# Schematic.net
KiCad netlist of a schematic drawn in EAGLE
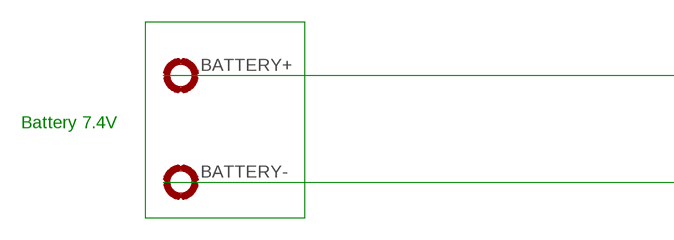
[diagram p0: schematic, sheet 1, part 1 of 2]
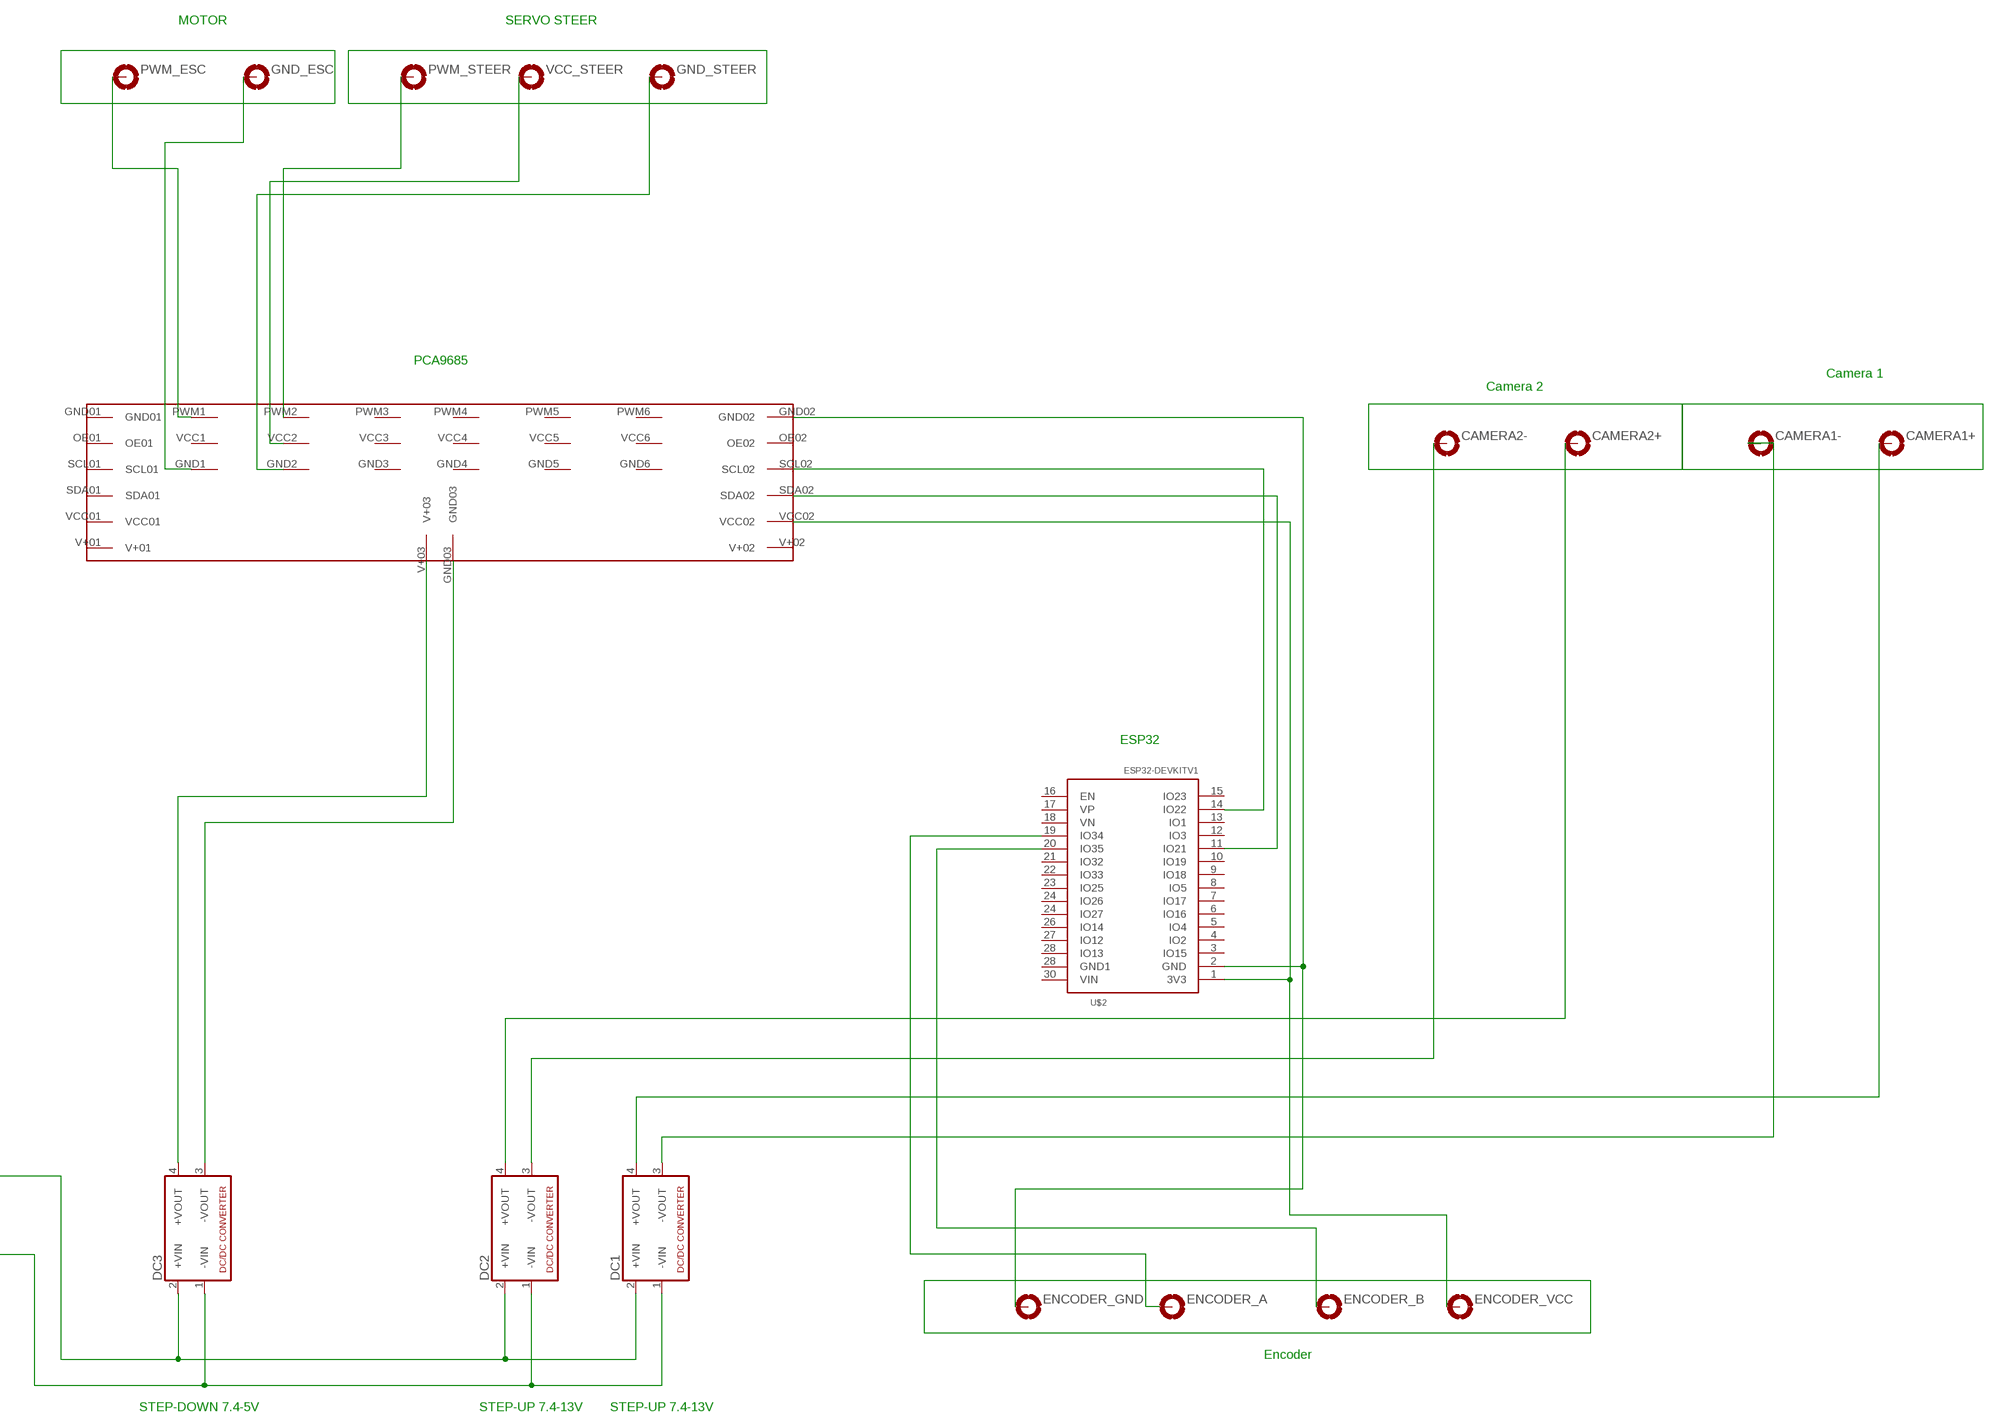
[diagram p1: schematic, sheet 1, part 2 of 2]

(export (version "E")
  (design (tool "Eeschema 10.0.6"))
  (components
    (comp (ref "BATTERY+")
      (value "MOUNT-PAD-ROUND2.8")
      (footprint "eagle-import:2,8-PAD")
      (libsource (lib "eagle-import") (part "MOUNT-PAD-ROUND2.8"))
    )
    (comp (ref "BATTERY-")
      (value "MOUNT-PAD-ROUND2.8")
      (footprint "eagle-import:2,8-PAD")
      (libsource (lib "eagle-import") (part "MOUNT-PAD-ROUND2.8"))
    )
    (comp (ref "CAMERA1+")
      (value "MOUNT-PAD-ROUND2.8")
      (footprint "eagle-import:2,8-PAD")
      (libsource (lib "eagle-import") (part "MOUNT-PAD-ROUND2.8"))
    )
    (comp (ref "CAMERA1-")
      (value "MOUNT-PAD-ROUND2.8")
      (footprint "eagle-import:2,8-PAD")
      (libsource (lib "eagle-import") (part "MOUNT-PAD-ROUND2.8"))
    )
    (comp (ref "CAMERA2+")
      (value "MOUNT-PAD-ROUND2.8")
      (footprint "eagle-import:2,8-PAD")
      (libsource (lib "eagle-import") (part "MOUNT-PAD-ROUND2.8"))
    )
    (comp (ref "CAMERA2-")
      (value "MOUNT-PAD-ROUND2.8")
      (footprint "eagle-import:2,8-PAD")
      (libsource (lib "eagle-import") (part "MOUNT-PAD-ROUND2.8"))
    )
    (comp (ref "DC1")
      (value "NME")
      (footprint "eagle-import:NME")
      (fields (field (name "MF") "C & D TECHNOLOGIES, INC") (field (name "MPN") "NME1205D"))
      (libsource (lib "eagle-import") (part "NME"))
    )
    (comp (ref "DC2")
      (value "NME")
      (footprint "eagle-import:NME")
      (fields (field (name "MF") "C & D TECHNOLOGIES, INC") (field (name "MPN") "NME1205D"))
      (libsource (lib "eagle-import") (part "NME"))
    )
    (comp (ref "DC3")
      (value "NME")
      (footprint "eagle-import:NME")
      (fields (field (name "MF") "C & D TECHNOLOGIES, INC") (field (name "MPN") "NME1205D"))
      (libsource (lib "eagle-import") (part "NME"))
    )
    (comp (ref "ENCODER_A")
      (value "MOUNT-PAD-ROUND2.8")
      (footprint "eagle-import:2,8-PAD")
      (libsource (lib "eagle-import") (part "MOUNT-PAD-ROUND2.8"))
    )
    (comp (ref "ENCODER_B")
      (value "MOUNT-PAD-ROUND2.8")
      (footprint "eagle-import:2,8-PAD")
      (libsource (lib "eagle-import") (part "MOUNT-PAD-ROUND2.8"))
    )
    (comp (ref "ENCODER_GND")
      (value "MOUNT-PAD-ROUND2.8")
      (footprint "eagle-import:2,8-PAD")
      (libsource (lib "eagle-import") (part "MOUNT-PAD-ROUND2.8"))
    )
    (comp (ref "ENCODER_VCC")
      (value "MOUNT-PAD-ROUND2.8")
      (footprint "eagle-import:2,8-PAD")
      (libsource (lib "eagle-import") (part "MOUNT-PAD-ROUND2.8"))
    )
    (comp (ref "GND_ESC")
      (value "MOUNT-PAD-ROUND2.8")
      (footprint "eagle-import:2,8-PAD")
      (libsource (lib "eagle-import") (part "MOUNT-PAD-ROUND2.8"))
    )
    (comp (ref "GND_STEER")
      (value "MOUNT-PAD-ROUND2.8")
      (footprint "eagle-import:2,8-PAD")
      (libsource (lib "eagle-import") (part "MOUNT-PAD-ROUND2.8"))
    )
    (comp (ref "PWM_ESC")
      (value "MOUNT-PAD-ROUND2.8")
      (footprint "eagle-import:2,8-PAD")
      (libsource (lib "eagle-import") (part "MOUNT-PAD-ROUND2.8"))
    )
    (comp (ref "PWM_STEER")
      (value "MOUNT-PAD-ROUND2.8")
      (footprint "eagle-import:2,8-PAD")
      (libsource (lib "eagle-import") (part "MOUNT-PAD-ROUND2.8"))
    )
    (comp (ref "U$1")
      (value "PCA9685PCA9685")
      (footprint "eagle-import:DIP5918W53P254L2279H300Q12B")
      (libsource (lib "eagle-import") (part "PCA9685PCA9685"))
    )
    (comp (ref "U$2")
      (value "ESP32DEVKITV1")
      (footprint "eagle-import:ESP32-DEVKITV1")
      (libsource (lib "eagle-import") (part "ESP32DEVKITV1"))
    )
    (comp (ref "VCC_STEER")
      (value "MOUNT-PAD-ROUND2.8")
      (footprint "eagle-import:2,8-PAD")
      (libsource (lib "eagle-import") (part "MOUNT-PAD-ROUND2.8"))
    )
  )
  (nets
    (net (code "1") (name "Net-(BATTERY+-MOUNT)") (class "Default")
      (node (ref "BATTERY+") (pin "B2,8") (pinfunction "MOUNT_B2,8") (pintype "passive"))
      (node (ref "DC1") (pin "2") (pinfunction "+VIN_2") (pintype "passive"))
      (node (ref "DC2") (pin "2") (pinfunction "+VIN_2") (pintype "passive"))
      (node (ref "DC3") (pin "2") (pinfunction "+VIN_2") (pintype "passive"))
    )
    (net (code "2") (name "Net-(BATTERY--MOUNT)") (class "Default")
      (node (ref "BATTERY-") (pin "B2,8") (pinfunction "MOUNT_B2,8") (pintype "passive"))
      (node (ref "DC1") (pin "1") (pinfunction "-VIN_1") (pintype "passive"))
      (node (ref "DC2") (pin "1") (pinfunction "-VIN_1") (pintype "passive"))
      (node (ref "DC3") (pin "1") (pinfunction "-VIN_1") (pintype "passive"))
    )
    (net (code "3") (name "Net-(CAMERA1+-MOUNT)") (class "Default")
      (node (ref "CAMERA1+") (pin "B2,8") (pinfunction "MOUNT_B2,8") (pintype "passive"))
      (node (ref "DC1") (pin "4") (pinfunction "+VOUT_4") (pintype "passive"))
    )
    (net (code "4") (name "Net-(CAMERA1--MOUNT)") (class "Default")
      (node (ref "CAMERA1-") (pin "B2,8") (pinfunction "MOUNT_B2,8") (pintype "passive"))
      (node (ref "DC1") (pin "3") (pinfunction "-VOUT_3") (pintype "passive"))
    )
    (net (code "5") (name "Net-(CAMERA2+-MOUNT)") (class "Default")
      (node (ref "CAMERA2+") (pin "B2,8") (pinfunction "MOUNT_B2,8") (pintype "passive"))
      (node (ref "DC2") (pin "4") (pinfunction "+VOUT_4") (pintype "passive"))
    )
    (net (code "6") (name "Net-(CAMERA2--MOUNT)") (class "Default")
      (node (ref "CAMERA2-") (pin "B2,8") (pinfunction "MOUNT_B2,8") (pintype "passive"))
      (node (ref "DC2") (pin "3") (pinfunction "-VOUT_3") (pintype "passive"))
    )
    (net (code "7") (name "Net-(DC3-+VOUT)") (class "Default")
      (node (ref "DC3") (pin "4") (pinfunction "+VOUT_4") (pintype "passive"))
      (node (ref "U$1") (pin "V+03") (pinfunction "V+03_V+03") (pintype "bidirectional"))
    )
    (net (code "8") (name "Net-(DC3--VOUT)") (class "Default")
      (node (ref "DC3") (pin "3") (pinfunction "-VOUT_3") (pintype "passive"))
      (node (ref "U$1") (pin "GND03") (pinfunction "GND03_GND03") (pintype "bidirectional"))
    )
    (net (code "9") (name "Net-(ENCODER_A-MOUNT)") (class "Default")
      (node (ref "ENCODER_A") (pin "B2,8") (pinfunction "MOUNT_B2,8") (pintype "passive"))
      (node (ref "U$2") (pin "19") (pinfunction "IO34_19") (pintype "bidirectional"))
    )
    (net (code "10") (name "Net-(ENCODER_B-MOUNT)") (class "Default")
      (node (ref "ENCODER_B") (pin "B2,8") (pinfunction "MOUNT_B2,8") (pintype "passive"))
      (node (ref "U$2") (pin "20") (pinfunction "IO35_20") (pintype "bidirectional"))
    )
    (net (code "11") (name "Net-(ENCODER_GND-MOUNT)") (class "Default")
      (node (ref "ENCODER_GND") (pin "B2,8") (pinfunction "MOUNT_B2,8") (pintype "passive"))
      (node (ref "U$1") (pin "GND02") (pinfunction "GND02_GND02") (pintype "bidirectional"))
      (node (ref "U$2") (pin "2") (pinfunction "GND_2") (pintype "bidirectional"))
    )
    (net (code "12") (name "Net-(ENCODER_VCC-MOUNT)") (class "Default")
      (node (ref "ENCODER_VCC") (pin "B2,8") (pinfunction "MOUNT_B2,8") (pintype "passive"))
      (node (ref "U$1") (pin "VCC02") (pinfunction "VCC02_VCC02") (pintype "bidirectional"))
      (node (ref "U$2") (pin "1") (pinfunction "3V3_1") (pintype "bidirectional"))
    )
    (net (code "13") (name "Net-(GND_ESC-MOUNT)") (class "Default")
      (node (ref "GND_ESC") (pin "B2,8") (pinfunction "MOUNT_B2,8") (pintype "passive"))
      (node (ref "U$1") (pin "GND1") (pinfunction "GND$1_GND1") (pintype "bidirectional"))
    )
    (net (code "14") (name "Net-(GND_STEER-MOUNT)") (class "Default")
      (node (ref "GND_STEER") (pin "B2,8") (pinfunction "MOUNT_B2,8") (pintype "passive"))
      (node (ref "U$1") (pin "GND2") (pinfunction "GND$2_GND2") (pintype "bidirectional"))
    )
    (net (code "15") (name "Net-(PWM_ESC-MOUNT)") (class "Default")
      (node (ref "PWM_ESC") (pin "B2,8") (pinfunction "MOUNT_B2,8") (pintype "passive"))
      (node (ref "U$1") (pin "PWM1") (pinfunction "PWM$1_PWM1") (pintype "bidirectional"))
    )
    (net (code "16") (name "Net-(PWM_STEER-MOUNT)") (class "Default")
      (node (ref "PWM_STEER") (pin "B2,8") (pinfunction "MOUNT_B2,8") (pintype "passive"))
      (node (ref "U$1") (pin "PWM2") (pinfunction "PWM$2_PWM2") (pintype "bidirectional"))
    )
    (net (code "17") (name "Net-(U$1-VCC$2)") (class "Default")
      (node (ref "U$1") (pin "VCC2") (pinfunction "VCC$2_VCC2") (pintype "bidirectional"))
      (node (ref "VCC_STEER") (pin "B2,8") (pinfunction "MOUNT_B2,8") (pintype "passive"))
    )
    (net (code "18") (name "Net-(U$2-IO21)") (class "Default")
      (node (ref "U$1") (pin "SDA02") (pinfunction "SDA02_SDA02") (pintype "bidirectional"))
      (node (ref "U$2") (pin "11") (pinfunction "IO21_11") (pintype "bidirectional"))
    )
    (net (code "19") (name "Net-(U$2-IO22)") (class "Default")
      (node (ref "U$1") (pin "SCL02") (pinfunction "SCL02_SCL02") (pintype "bidirectional"))
      (node (ref "U$2") (pin "14") (pinfunction "IO22_14") (pintype "bidirectional"))
    )
    (net (code "20") (name "unconnected-(U$1-GND$3-PadGND3)") (class "Default")
      (node (ref "U$1") (pin "GND3") (pinfunction "GND$3_GND3") (pintype "bidirectional"))
    )
    (net (code "21") (name "unconnected-(U$1-GND$4-PadGND4)") (class "Default")
      (node (ref "U$1") (pin "GND4") (pinfunction "GND$4_GND4") (pintype "bidirectional"))
    )
    (net (code "22") (name "unconnected-(U$1-GND$5-PadGND5)") (class "Default")
      (node (ref "U$1") (pin "GND5") (pinfunction "GND$5_GND5") (pintype "bidirectional"))
    )
    (net (code "23") (name "unconnected-(U$1-GND$6-PadGND6)") (class "Default")
      (node (ref "U$1") (pin "GND6") (pinfunction "GND$6_GND6") (pintype "bidirectional"))
    )
    (net (code "24") (name "unconnected-(U$1-PWM$3-PadPWM3)") (class "Default")
      (node (ref "U$1") (pin "PWM3") (pinfunction "PWM$3_PWM3") (pintype "bidirectional"))
    )
    (net (code "25") (name "unconnected-(U$1-PWM$4-PadPWM4)") (class "Default")
      (node (ref "U$1") (pin "PWM4") (pinfunction "PWM$4_PWM4") (pintype "bidirectional"))
    )
    (net (code "26") (name "unconnected-(U$1-PWM$5-PadPWM5)") (class "Default")
      (node (ref "U$1") (pin "PWM5") (pinfunction "PWM$5_PWM5") (pintype "bidirectional"))
    )
    (net (code "27") (name "unconnected-(U$1-PWM$6-PadPWM6)") (class "Default")
      (node (ref "U$1") (pin "PWM6") (pinfunction "PWM$6_PWM6") (pintype "bidirectional"))
    )
    (net (code "28") (name "unconnected-(U$1-PadGND01)") (class "Default")
      (node (ref "U$1") (pin "GND01") (pinfunction "GND01_GND01") (pintype "bidirectional"))
    )
    (net (code "29") (name "unconnected-(U$1-PadOE01)") (class "Default")
      (node (ref "U$1") (pin "OE01") (pinfunction "OE01_OE01") (pintype "bidirectional"))
    )
    (net (code "30") (name "unconnected-(U$1-PadOE02)") (class "Default")
      (node (ref "U$1") (pin "OE02") (pinfunction "OE02_OE02") (pintype "bidirectional"))
    )
    (net (code "31") (name "unconnected-(U$1-PadSCL01)") (class "Default")
      (node (ref "U$1") (pin "SCL01") (pinfunction "SCL01_SCL01") (pintype "bidirectional"))
    )
    (net (code "32") (name "unconnected-(U$1-PadSDA01)") (class "Default")
      (node (ref "U$1") (pin "SDA01") (pinfunction "SDA01_SDA01") (pintype "bidirectional"))
    )
    (net (code "33") (name "unconnected-(U$1-PadV+01)") (class "Default")
      (node (ref "U$1") (pin "V+01") (pinfunction "V+01_V+01") (pintype "bidirectional"))
    )
    (net (code "34") (name "unconnected-(U$1-PadV+02)") (class "Default")
      (node (ref "U$1") (pin "V+02") (pinfunction "V+02_V+02") (pintype "bidirectional"))
    )
    (net (code "35") (name "unconnected-(U$1-PadVCC01)") (class "Default")
      (node (ref "U$1") (pin "VCC01") (pinfunction "VCC01_VCC01") (pintype "bidirectional"))
    )
    (net (code "36") (name "unconnected-(U$1-VCC$1-PadVCC1)") (class "Default")
      (node (ref "U$1") (pin "VCC1") (pinfunction "VCC$1_VCC1") (pintype "bidirectional"))
    )
    (net (code "37") (name "unconnected-(U$1-VCC$3-PadVCC3)") (class "Default")
      (node (ref "U$1") (pin "VCC3") (pinfunction "VCC$3_VCC3") (pintype "bidirectional"))
    )
    (net (code "38") (name "unconnected-(U$1-VCC$4-PadVCC4)") (class "Default")
      (node (ref "U$1") (pin "VCC4") (pinfunction "VCC$4_VCC4") (pintype "bidirectional"))
    )
    (net (code "39") (name "unconnected-(U$1-VCC$5-PadVCC5)") (class "Default")
      (node (ref "U$1") (pin "VCC5") (pinfunction "VCC$5_VCC5") (pintype "bidirectional"))
    )
    (net (code "40") (name "unconnected-(U$1-VCC$6-PadVCC6)") (class "Default")
      (node (ref "U$1") (pin "VCC6") (pinfunction "VCC$6_VCC6") (pintype "bidirectional"))
    )
    (net (code "41") (name "unconnected-(U$2-EN-Pad16)") (class "Default")
      (node (ref "U$2") (pin "16") (pinfunction "EN_16") (pintype "bidirectional"))
    )
    (net (code "42") (name "unconnected-(U$2-GND1-Pad28)") (class "Default")
      (node (ref "U$2") (pin "28") (pinfunction "GND1_28") (pintype "bidirectional"))
    )
    (net (code "43") (name "unconnected-(U$2-IO1-Pad13)") (class "Default")
      (node (ref "U$2") (pin "13") (pinfunction "IO1_13") (pintype "bidirectional"))
    )
    (net (code "44") (name "unconnected-(U$2-IO2-Pad4)") (class "Default")
      (node (ref "U$2") (pin "4") (pinfunction "IO2_4") (pintype "bidirectional"))
    )
    (net (code "45") (name "unconnected-(U$2-IO3-Pad12)") (class "Default")
      (node (ref "U$2") (pin "12") (pinfunction "IO3_12") (pintype "bidirectional"))
    )
    (net (code "46") (name "unconnected-(U$2-IO4-Pad5)") (class "Default")
      (node (ref "U$2") (pin "5") (pinfunction "IO4_5") (pintype "bidirectional"))
    )
    (net (code "47") (name "unconnected-(U$2-IO5-Pad8)") (class "Default")
      (node (ref "U$2") (pin "8") (pinfunction "IO5_8") (pintype "bidirectional"))
    )
    (net (code "48") (name "unconnected-(U$2-IO12-Pad27)") (class "Default")
      (node (ref "U$2") (pin "27") (pinfunction "IO12_27") (pintype "bidirectional"))
    )
    (net (code "49") (name "unconnected-(U$2-IO13-Pad28)") (class "Default")
      (node (ref "U$2") (pin "28") (pinfunction "IO13_28") (pintype "bidirectional"))
    )
    (net (code "50") (name "unconnected-(U$2-IO14-Pad26)") (class "Default")
      (node (ref "U$2") (pin "26") (pinfunction "IO14_26") (pintype "bidirectional"))
    )
    (net (code "51") (name "unconnected-(U$2-IO15-Pad3)") (class "Default")
      (node (ref "U$2") (pin "3") (pinfunction "IO15_3") (pintype "bidirectional"))
    )
    (net (code "52") (name "unconnected-(U$2-IO16-Pad6)") (class "Default")
      (node (ref "U$2") (pin "6") (pinfunction "IO16_6") (pintype "bidirectional"))
    )
    (net (code "53") (name "unconnected-(U$2-IO17-Pad7)") (class "Default")
      (node (ref "U$2") (pin "7") (pinfunction "IO17_7") (pintype "bidirectional"))
    )
    (net (code "54") (name "unconnected-(U$2-IO18-Pad9)") (class "Default")
      (node (ref "U$2") (pin "9") (pinfunction "IO18_9") (pintype "bidirectional"))
    )
    (net (code "55") (name "unconnected-(U$2-IO19-Pad10)") (class "Default")
      (node (ref "U$2") (pin "10") (pinfunction "IO19_10") (pintype "bidirectional"))
    )
    (net (code "56") (name "unconnected-(U$2-IO23-Pad15)") (class "Default")
      (node (ref "U$2") (pin "15") (pinfunction "IO23_15") (pintype "bidirectional"))
    )
    (net (code "57") (name "unconnected-(U$2-IO25-Pad23)") (class "Default")
      (node (ref "U$2") (pin "23") (pinfunction "IO25_23") (pintype "bidirectional"))
    )
    (net (code "58") (name "unconnected-(U$2-IO26-Pad24)") (class "Default")
      (node (ref "U$2") (pin "24") (pinfunction "IO26_24") (pintype "bidirectional"))
    )
    (net (code "59") (name "unconnected-(U$2-IO27-Pad24)") (class "Default")
      (node (ref "U$2") (pin "24") (pinfunction "IO27_24") (pintype "bidirectional"))
    )
    (net (code "60") (name "unconnected-(U$2-IO32-Pad21)") (class "Default")
      (node (ref "U$2") (pin "21") (pinfunction "IO32_21") (pintype "bidirectional"))
    )
    (net (code "61") (name "unconnected-(U$2-IO33-Pad22)") (class "Default")
      (node (ref "U$2") (pin "22") (pinfunction "IO33_22") (pintype "bidirectional"))
    )
    (net (code "62") (name "unconnected-(U$2-VIN-Pad30)") (class "Default")
      (node (ref "U$2") (pin "30") (pinfunction "VIN_30") (pintype "bidirectional"))
    )
    (net (code "63") (name "unconnected-(U$2-VN-Pad18)") (class "Default")
      (node (ref "U$2") (pin "18") (pinfunction "VN_18") (pintype "bidirectional"))
    )
    (net (code "64") (name "unconnected-(U$2-VP-Pad17)") (class "Default")
      (node (ref "U$2") (pin "17") (pinfunction "VP_17") (pintype "bidirectional"))
    )
  )
)
